# power.net
KiCad netlist of a schematic drawn in EAGLE
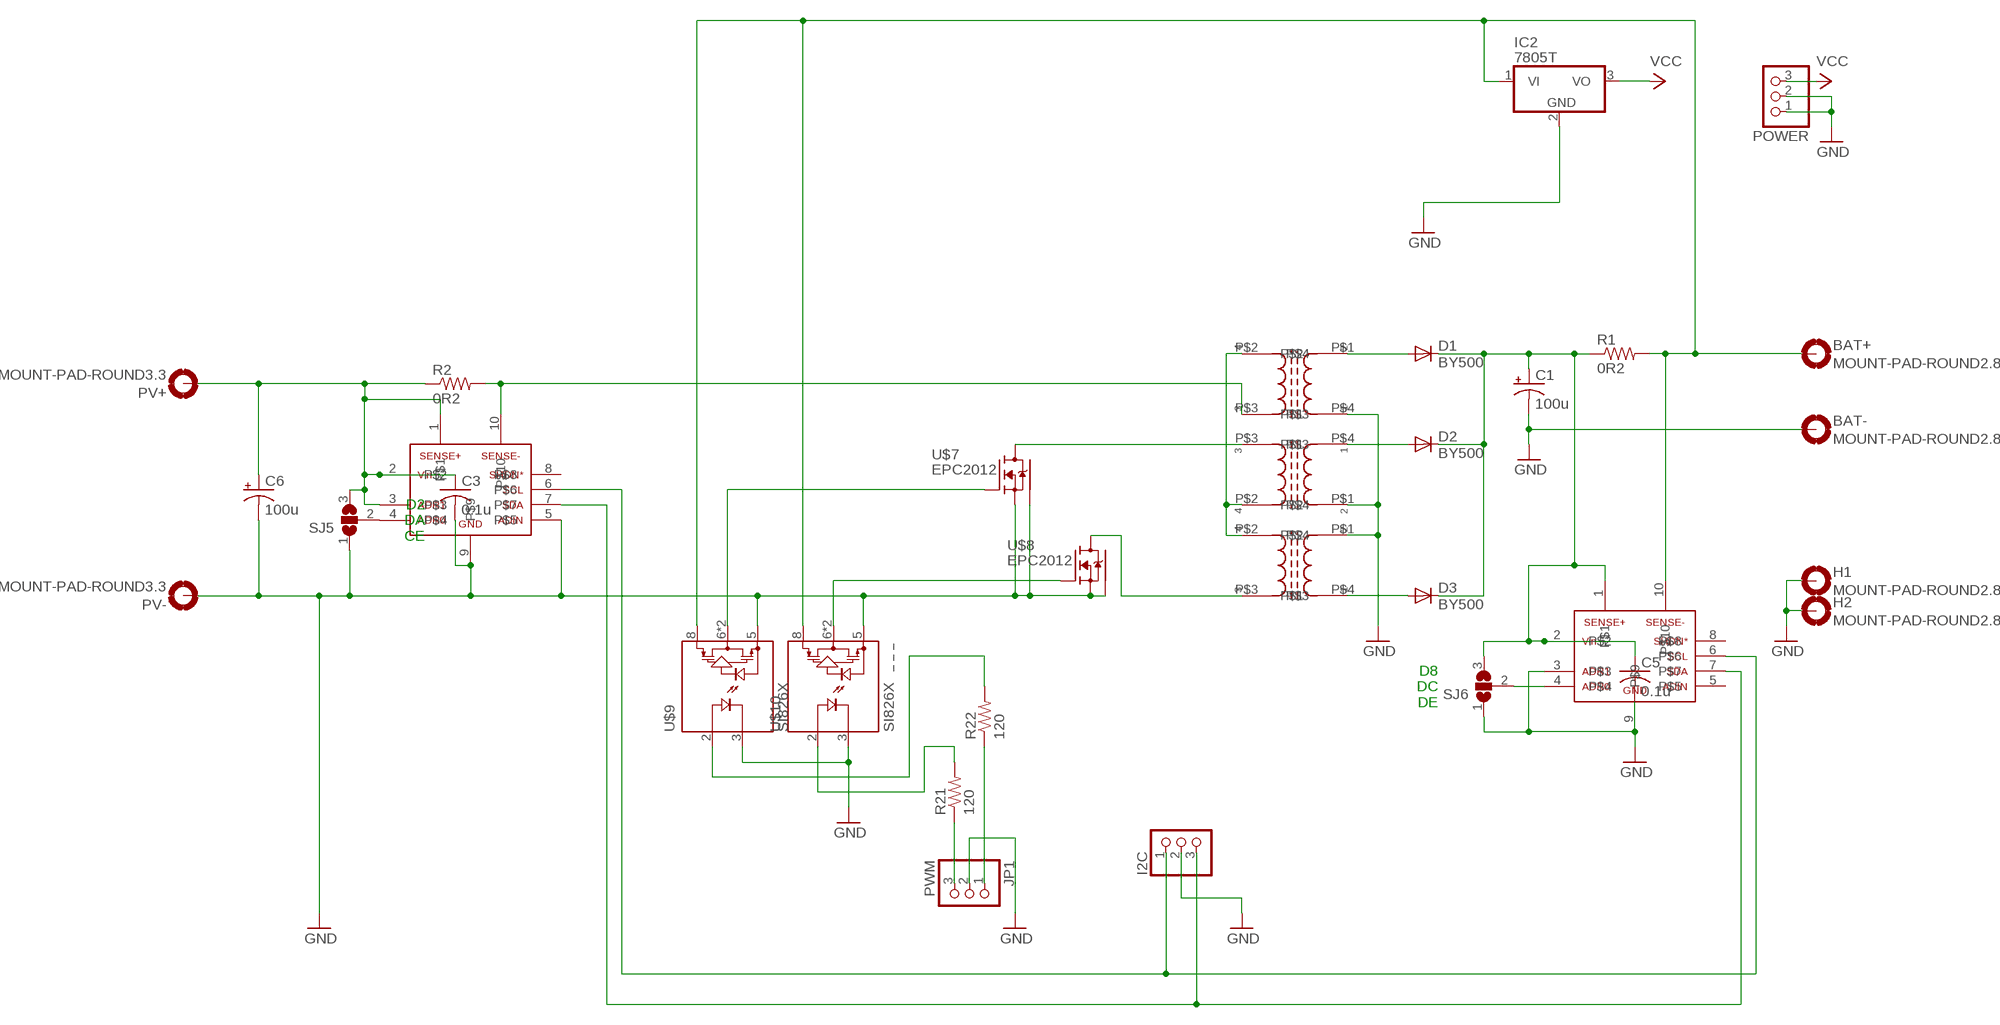
[diagram p0: schematic, sheet 1]

(export (version "E")
  (design (tool "Eeschema 10.0.6"))
  (components
    (comp (ref "BAT+")
      (value "MOUNT-PAD-ROUND2.8")
      (footprint "eagle-import:2,8-PAD")
      (libsource (lib "eagle-import") (part "MOUNT-PAD-ROUND2.8"))
    )
    (comp (ref "BAT-")
      (value "MOUNT-PAD-ROUND2.8")
      (footprint "eagle-import:2,8-PAD")
      (libsource (lib "eagle-import") (part "MOUNT-PAD-ROUND2.8"))
    )
    (comp (ref "C1")
      (value "100u")
      (footprint "eagle-import:E5-10,5")
      (libsource (lib "eagle-import") (part "CPOL-USE5-10.5"))
    )
    (comp (ref "C3")
      (value "0.1u")
      (footprint "eagle-import:C0603K")
      (libsource (lib "eagle-import") (part "C-USC0603K"))
    )
    (comp (ref "C5")
      (value "0.1u")
      (footprint "eagle-import:C0603K")
      (libsource (lib "eagle-import") (part "C-USC0603K"))
    )
    (comp (ref "C6")
      (value "100u")
      (footprint "eagle-import:E5-10,5")
      (libsource (lib "eagle-import") (part "CPOL-USE5-10.5"))
    )
    (comp (ref "D1")
      (value "BY500")
      (footprint "eagle-import:DO201-15")
      (libsource (lib "eagle-import") (part "BY500"))
    )
    (comp (ref "D2")
      (value "BY500")
      (footprint "eagle-import:DO201-15")
      (libsource (lib "eagle-import") (part "BY500"))
    )
    (comp (ref "D3")
      (value "BY500")
      (footprint "eagle-import:DO201-15")
      (libsource (lib "eagle-import") (part "BY500"))
    )
    (comp (ref "H1")
      (value "MOUNT-PAD-ROUND2.8")
      (footprint "eagle-import:2,8-PAD")
      (libsource (lib "eagle-import") (part "MOUNT-PAD-ROUND2.8"))
    )
    (comp (ref "H2")
      (value "MOUNT-PAD-ROUND2.8")
      (footprint "eagle-import:2,8-PAD")
      (libsource (lib "eagle-import") (part "MOUNT-PAD-ROUND2.8"))
    )
    (comp (ref "I2C")
      (value "PINHD-1X3")
      (footprint "eagle-import:1X03")
      (libsource (lib "eagle-import") (part "PINHD-1X3"))
    )
    (comp (ref "IC2")
      (value "7805T")
      (footprint "eagle-import:TO220H")
      (libsource (lib "eagle-import") (part "78T05"))
    )
    (comp (ref "JP1")
      (value "PWM")
      (footprint "eagle-import:1X03")
      (libsource (lib "eagle-import") (part "PINHD-1X3"))
    )
    (comp (ref "POWER")
      (value "PINHD-1X3")
      (footprint "eagle-import:1X03")
      (libsource (lib "eagle-import") (part "PINHD-1X3"))
    )
    (comp (ref "PV+")
      (value "MOUNT-PAD-ROUND3.3")
      (footprint "eagle-import:3,3-PAD")
      (libsource (lib "eagle-import") (part "MOUNT-PAD-ROUND3.3"))
    )
    (comp (ref "PV-")
      (value "MOUNT-PAD-ROUND3.3")
      (footprint "eagle-import:3,3-PAD")
      (libsource (lib "eagle-import") (part "MOUNT-PAD-ROUND3.3"))
    )
    (comp (ref "R1")
      (value "0R2")
      (footprint "eagle-import:R1206")
      (libsource (lib "eagle-import") (part "R-US_R1206"))
    )
    (comp (ref "R2")
      (value "0R2")
      (footprint "eagle-import:R1206")
      (libsource (lib "eagle-import") (part "R-US_R1206"))
    )
    (comp (ref "R21")
      (value "120")
      (footprint "eagle-import:R0603")
      (libsource (lib "eagle-import") (part "R-US_R0603"))
    )
    (comp (ref "R22")
      (value "120")
      (footprint "eagle-import:R0603")
      (libsource (lib "eagle-import") (part "R-US_R0603"))
    )
    (comp (ref "SJ5")
      (value "SJ2W")
      (footprint "eagle-import:SJ_2")
      (libsource (lib "eagle-import") (part "SJ2W"))
    )
    (comp (ref "SJ6")
      (value "SJ2W")
      (footprint "eagle-import:SJ_2")
      (libsource (lib "eagle-import") (part "SJ2W"))
    )
    (comp (ref "U$1")
      (value "LTC4151")
      (footprint "eagle-import:MSOP10")
      (libsource (lib "eagle-import") (part "LTC4151"))
    )
    (comp (ref "U$2")
      (value "LTC4151")
      (footprint "eagle-import:MSOP10")
      (libsource (lib "eagle-import") (part "LTC4151"))
    )
    (comp (ref "U$3")
      (value "PLH10AN2211R5P2B")
      (footprint "eagle-import:L10-13")
      (libsource (lib "eagle-import") (part "PLH10AN2211R5P2B"))
    )
    (comp (ref "U$4")
      (value "TLF14CBH3321R0K1")
      (footprint "eagle-import:L13-17")
      (libsource (lib "eagle-import") (part "TLF14CBH3321R0K1"))
    )
    (comp (ref "U$5")
      (value "TLF14CBH3321R0K1")
      (footprint "eagle-import:L13-17")
      (libsource (lib "eagle-import") (part "TLF14CBH3321R0K1"))
    )
    (comp (ref "U$7")
      (value "EPC2012")
      (footprint "eagle-import:EGAN-DIE-7")
      (libsource (lib "eagle-import") (part "EPC2012"))
    )
    (comp (ref "U$8")
      (value "EPC2012")
      (footprint "eagle-import:EGAN-DIE-7")
      (libsource (lib "eagle-import") (part "EPC2012"))
    )
    (comp (ref "U$9")
      (value "SI826X")
      (footprint "eagle-import:SO08")
      (libsource (lib "eagle-import") (part "SI826X"))
    )
    (comp (ref "U$10")
      (value "SI826X")
      (footprint "eagle-import:SO08")
      (libsource (lib "eagle-import") (part "SI826X"))
    )
  )
  (nets
    (net (code "1") (name "GND") (class "Default")
      (node (ref "BAT-") (pin "B2,8") (pinfunction "MOUNT_B2,8") (pintype "passive"))
      (node (ref "C1") (pin "-") (pinfunction "-_-") (pintype "passive"))
      (node (ref "C3") (pin "2") (pinfunction "2_2") (pintype "passive"))
      (node (ref "C5") (pin "2") (pinfunction "2_2") (pintype "passive"))
      (node (ref "C6") (pin "-") (pinfunction "-_-") (pintype "passive"))
      (node (ref "H1") (pin "B2,8") (pinfunction "MOUNT_B2,8") (pintype "passive"))
      (node (ref "H2") (pin "B2,8") (pinfunction "MOUNT_B2,8") (pintype "passive"))
      (node (ref "I2C") (pin "2") (pinfunction "2_2") (pintype "passive"))
      (node (ref "IC2") (pin "2") (pinfunction "GND_2") (pintype "passive"))
      (node (ref "JP1") (pin "2") (pinfunction "2_2") (pintype "passive"))
      (node (ref "POWER") (pin "1") (pinfunction "1_1") (pintype "passive"))
      (node (ref "POWER") (pin "2") (pinfunction "2_2") (pintype "passive"))
      (node (ref "PV-") (pin "B3,3") (pinfunction "MOUNT_B3,3") (pintype "passive"))
      (node (ref "SJ5") (pin "1") (pinfunction "1_1") (pintype "passive"))
      (node (ref "SJ6") (pin "1") (pinfunction "1_1") (pintype "passive"))
      (node (ref "U$1") (pin "5") (pinfunction "P$5_5") (pintype "bidirectional"))
      (node (ref "U$1") (pin "9") (pinfunction "P$9_9") (pintype "bidirectional"))
      (node (ref "U$10") (pin "3") (pinfunction "GND1_3") (pintype "passive"))
      (node (ref "U$10") (pin "5") (pinfunction "GND2_5") (pintype "passive"))
      (node (ref "U$2") (pin "3") (pinfunction "P$3_3") (pintype "bidirectional"))
      (node (ref "U$2") (pin "9") (pinfunction "P$9_9") (pintype "bidirectional"))
      (node (ref "U$3") (pin "P$4") (pinfunction "P$1_P$4") (pintype "bidirectional"))
      (node (ref "U$4") (pin "P$1") (pinfunction "P$2_P$1") (pintype "bidirectional"))
      (node (ref "U$5") (pin "P$1") (pinfunction "P$2_P$1") (pintype "bidirectional"))
      (node (ref "U$7") (pin "SOURCE") (pinfunction "S_SOURCE") (pintype "passive"))
      (node (ref "U$7") (pin "SUBSTRATE") (pinfunction "SUBSTRATE_SUBSTRATE") (pintype "passive"))
      (node (ref "U$8") (pin "SOURCE") (pinfunction "S_SOURCE") (pintype "passive"))
      (node (ref "U$8") (pin "SUBSTRATE") (pinfunction "SUBSTRATE_SUBSTRATE") (pintype "passive"))
      (node (ref "U$9") (pin "3") (pinfunction "GND1_3") (pintype "passive"))
      (node (ref "U$9") (pin "5") (pinfunction "GND2_5") (pintype "passive"))
    )
    (net (code "2") (name "Net-(BAT+-MOUNT)") (class "Default")
      (node (ref "BAT+") (pin "B2,8") (pinfunction "MOUNT_B2,8") (pintype "passive"))
      (node (ref "IC2") (pin "1") (pinfunction "VI_1") (pintype "input"))
      (node (ref "R1") (pin "2") (pinfunction "2_2") (pintype "passive"))
      (node (ref "U$10") (pin "8") (pinfunction "VDD2_8") (pintype "passive"))
      (node (ref "U$2") (pin "10") (pinfunction "P$10_10") (pintype "bidirectional"))
      (node (ref "U$9") (pin "8") (pinfunction "VDD2_8") (pintype "passive"))
    )
    (net (code "3") (name "Net-(JP1-Pad1)") (class "Default")
      (node (ref "JP1") (pin "1") (pinfunction "1_1") (pintype "passive"))
      (node (ref "R22") (pin "1") (pinfunction "1_1") (pintype "passive"))
    )
    (net (code "4") (name "Net-(JP1-Pad3)") (class "Default")
      (node (ref "JP1") (pin "3") (pinfunction "3_3") (pintype "passive"))
      (node (ref "R21") (pin "1") (pinfunction "1_1") (pintype "passive"))
    )
    (net (code "5") (name "Net-(PV+-MOUNT)") (class "Default")
      (node (ref "C3") (pin "1") (pinfunction "1_1") (pintype "passive"))
      (node (ref "C6") (pin "+") (pinfunction "+_+") (pintype "passive"))
      (node (ref "PV+") (pin "B3,3") (pinfunction "MOUNT_B3,3") (pintype "passive"))
      (node (ref "R2") (pin "1") (pinfunction "1_1") (pintype "passive"))
      (node (ref "SJ5") (pin "3") (pinfunction "3_3") (pintype "passive"))
      (node (ref "U$1") (pin "1") (pinfunction "P$1_1") (pintype "bidirectional"))
      (node (ref "U$1") (pin "2") (pinfunction "P$2_2") (pintype "bidirectional"))
      (node (ref "U$1") (pin "3") (pinfunction "P$3_3") (pintype "bidirectional"))
    )
    (net (code "6") (name "Net-(U$1-P$4)") (class "Default")
      (node (ref "SJ5") (pin "2") (pinfunction "2_2") (pintype "passive"))
      (node (ref "U$1") (pin "4") (pinfunction "P$4_4") (pintype "bidirectional"))
    )
    (net (code "7") (name "Net-(U$1-P$6)") (class "Default")
      (node (ref "I2C") (pin "1") (pinfunction "1_1") (pintype "passive"))
      (node (ref "U$1") (pin "6") (pinfunction "P$6_6") (pintype "bidirectional"))
      (node (ref "U$2") (pin "6") (pinfunction "P$6_6") (pintype "bidirectional"))
    )
    (net (code "8") (name "Net-(U$1-P$7)") (class "Default")
      (node (ref "I2C") (pin "3") (pinfunction "3_3") (pintype "passive"))
      (node (ref "U$1") (pin "7") (pinfunction "P$7_7") (pintype "bidirectional"))
      (node (ref "U$2") (pin "7") (pinfunction "P$7_7") (pintype "bidirectional"))
    )
    (net (code "9") (name "Net-(U$1-P$10)") (class "Default")
      (node (ref "R2") (pin "2") (pinfunction "2_2") (pintype "passive"))
      (node (ref "U$1") (pin "10") (pinfunction "P$10_10") (pintype "bidirectional"))
      (node (ref "U$3") (pin "P$3") (pinfunction "P$3_P$3") (pintype "bidirectional"))
    )
    (net (code "10") (name "Net-(U$2-P$1)") (class "Default")
      (node (ref "C1") (pin "+") (pinfunction "+_+") (pintype "passive"))
      (node (ref "C5") (pin "1") (pinfunction "1_1") (pintype "passive"))
      (node (ref "D1") (pin "C") (pinfunction "C_C") (pintype "passive"))
      (node (ref "D2") (pin "C") (pinfunction "C_C") (pintype "passive"))
      (node (ref "D3") (pin "C") (pinfunction "C_C") (pintype "passive"))
      (node (ref "R1") (pin "1") (pinfunction "1_1") (pintype "passive"))
      (node (ref "SJ6") (pin "3") (pinfunction "3_3") (pintype "passive"))
      (node (ref "U$2") (pin "1") (pinfunction "P$1_1") (pintype "bidirectional"))
      (node (ref "U$2") (pin "2") (pinfunction "P$2_2") (pintype "bidirectional"))
    )
    (net (code "11") (name "Net-(U$2-P$4)") (class "Default")
      (node (ref "SJ6") (pin "2") (pinfunction "2_2") (pintype "passive"))
      (node (ref "U$2") (pin "4") (pinfunction "P$4_4") (pintype "bidirectional"))
    )
    (net (code "12") (name "Net-(U$3-P$2)") (class "Default")
      (node (ref "D1") (pin "A") (pinfunction "A_A") (pintype "passive"))
      (node (ref "U$3") (pin "P$1") (pinfunction "P$2_P$1") (pintype "bidirectional"))
    )
    (net (code "13") (name "Net-(U$3-P$4)") (class "Default")
      (node (ref "U$3") (pin "P$2") (pinfunction "P$4_P$2") (pintype "bidirectional"))
      (node (ref "U$4") (pin "P$2") (pinfunction "P$4_P$2") (pintype "bidirectional"))
      (node (ref "U$5") (pin "P$2") (pinfunction "P$4_P$2") (pintype "bidirectional"))
    )
    (net (code "14") (name "Net-(U$4-P$1)") (class "Default")
      (node (ref "D3") (pin "A") (pinfunction "A_A") (pintype "passive"))
      (node (ref "U$4") (pin "P$4") (pinfunction "P$1_P$4") (pintype "bidirectional"))
    )
    (net (code "15") (name "Net-(U$5-P$1)") (class "Default")
      (node (ref "D2") (pin "A") (pinfunction "A_A") (pintype "passive"))
      (node (ref "U$5") (pin "P$4") (pinfunction "P$1_P$4") (pintype "bidirectional"))
    )
    (net (code "16") (name "Net-(U$7-D)") (class "Default")
      (node (ref "U$5") (pin "P$3") (pinfunction "P$3_P$3") (pintype "bidirectional"))
      (node (ref "U$7") (pin "DRAIN") (pinfunction "D_DRAIN") (pintype "passive"))
    )
    (net (code "17") (name "Net-(U$7-G)") (class "Default")
      (node (ref "U$7") (pin "GATE") (pinfunction "G_GATE") (pintype "passive"))
      (node (ref "U$9") (pin "6") (pinfunction "VO_6") (pintype "passive"))
      (node (ref "U$9") (pin "7") (pinfunction "VO_7") (pintype "passive"))
    )
    (net (code "18") (name "Net-(U$8-D)") (class "Default")
      (node (ref "U$4") (pin "P$3") (pinfunction "P$3_P$3") (pintype "bidirectional"))
      (node (ref "U$8") (pin "DRAIN") (pinfunction "D_DRAIN") (pintype "passive"))
    )
    (net (code "19") (name "Net-(U$8-G)") (class "Default")
      (node (ref "U$10") (pin "6") (pinfunction "VO_6") (pintype "passive"))
      (node (ref "U$10") (pin "7") (pinfunction "VO_7") (pintype "passive"))
      (node (ref "U$8") (pin "GATE") (pinfunction "G_GATE") (pintype "passive"))
    )
    (net (code "20") (name "Net-(U$9-VI)") (class "Default")
      (node (ref "R22") (pin "2") (pinfunction "2_2") (pintype "passive"))
      (node (ref "U$9") (pin "2") (pinfunction "VI_2") (pintype "input"))
    )
    (net (code "21") (name "Net-(U$10-VI)") (class "Default")
      (node (ref "R21") (pin "2") (pinfunction "2_2") (pintype "passive"))
      (node (ref "U$10") (pin "2") (pinfunction "VI_2") (pintype "input"))
    )
    (net (code "22") (name "VCC") (class "Default")
      (node (ref "IC2") (pin "3") (pinfunction "VO_3") (pintype "passive"))
      (node (ref "POWER") (pin "3") (pinfunction "3_3") (pintype "passive"))
    )
    (net (code "23") (name "unconnected-(U$1-P$8-Pad8)") (class "Default")
      (node (ref "U$1") (pin "8") (pinfunction "P$8_8") (pintype "bidirectional"))
    )
    (net (code "24") (name "unconnected-(U$2-P$5-Pad5)") (class "Default")
      (node (ref "U$2") (pin "5") (pinfunction "P$5_5") (pintype "bidirectional"))
    )
    (net (code "25") (name "unconnected-(U$2-P$8-Pad8)") (class "Default")
      (node (ref "U$2") (pin "8") (pinfunction "P$8_8") (pintype "bidirectional"))
    )
  )
)
